# ServoDriverV2.net
KiCad netlist of a schematic drawn in EasyEDA
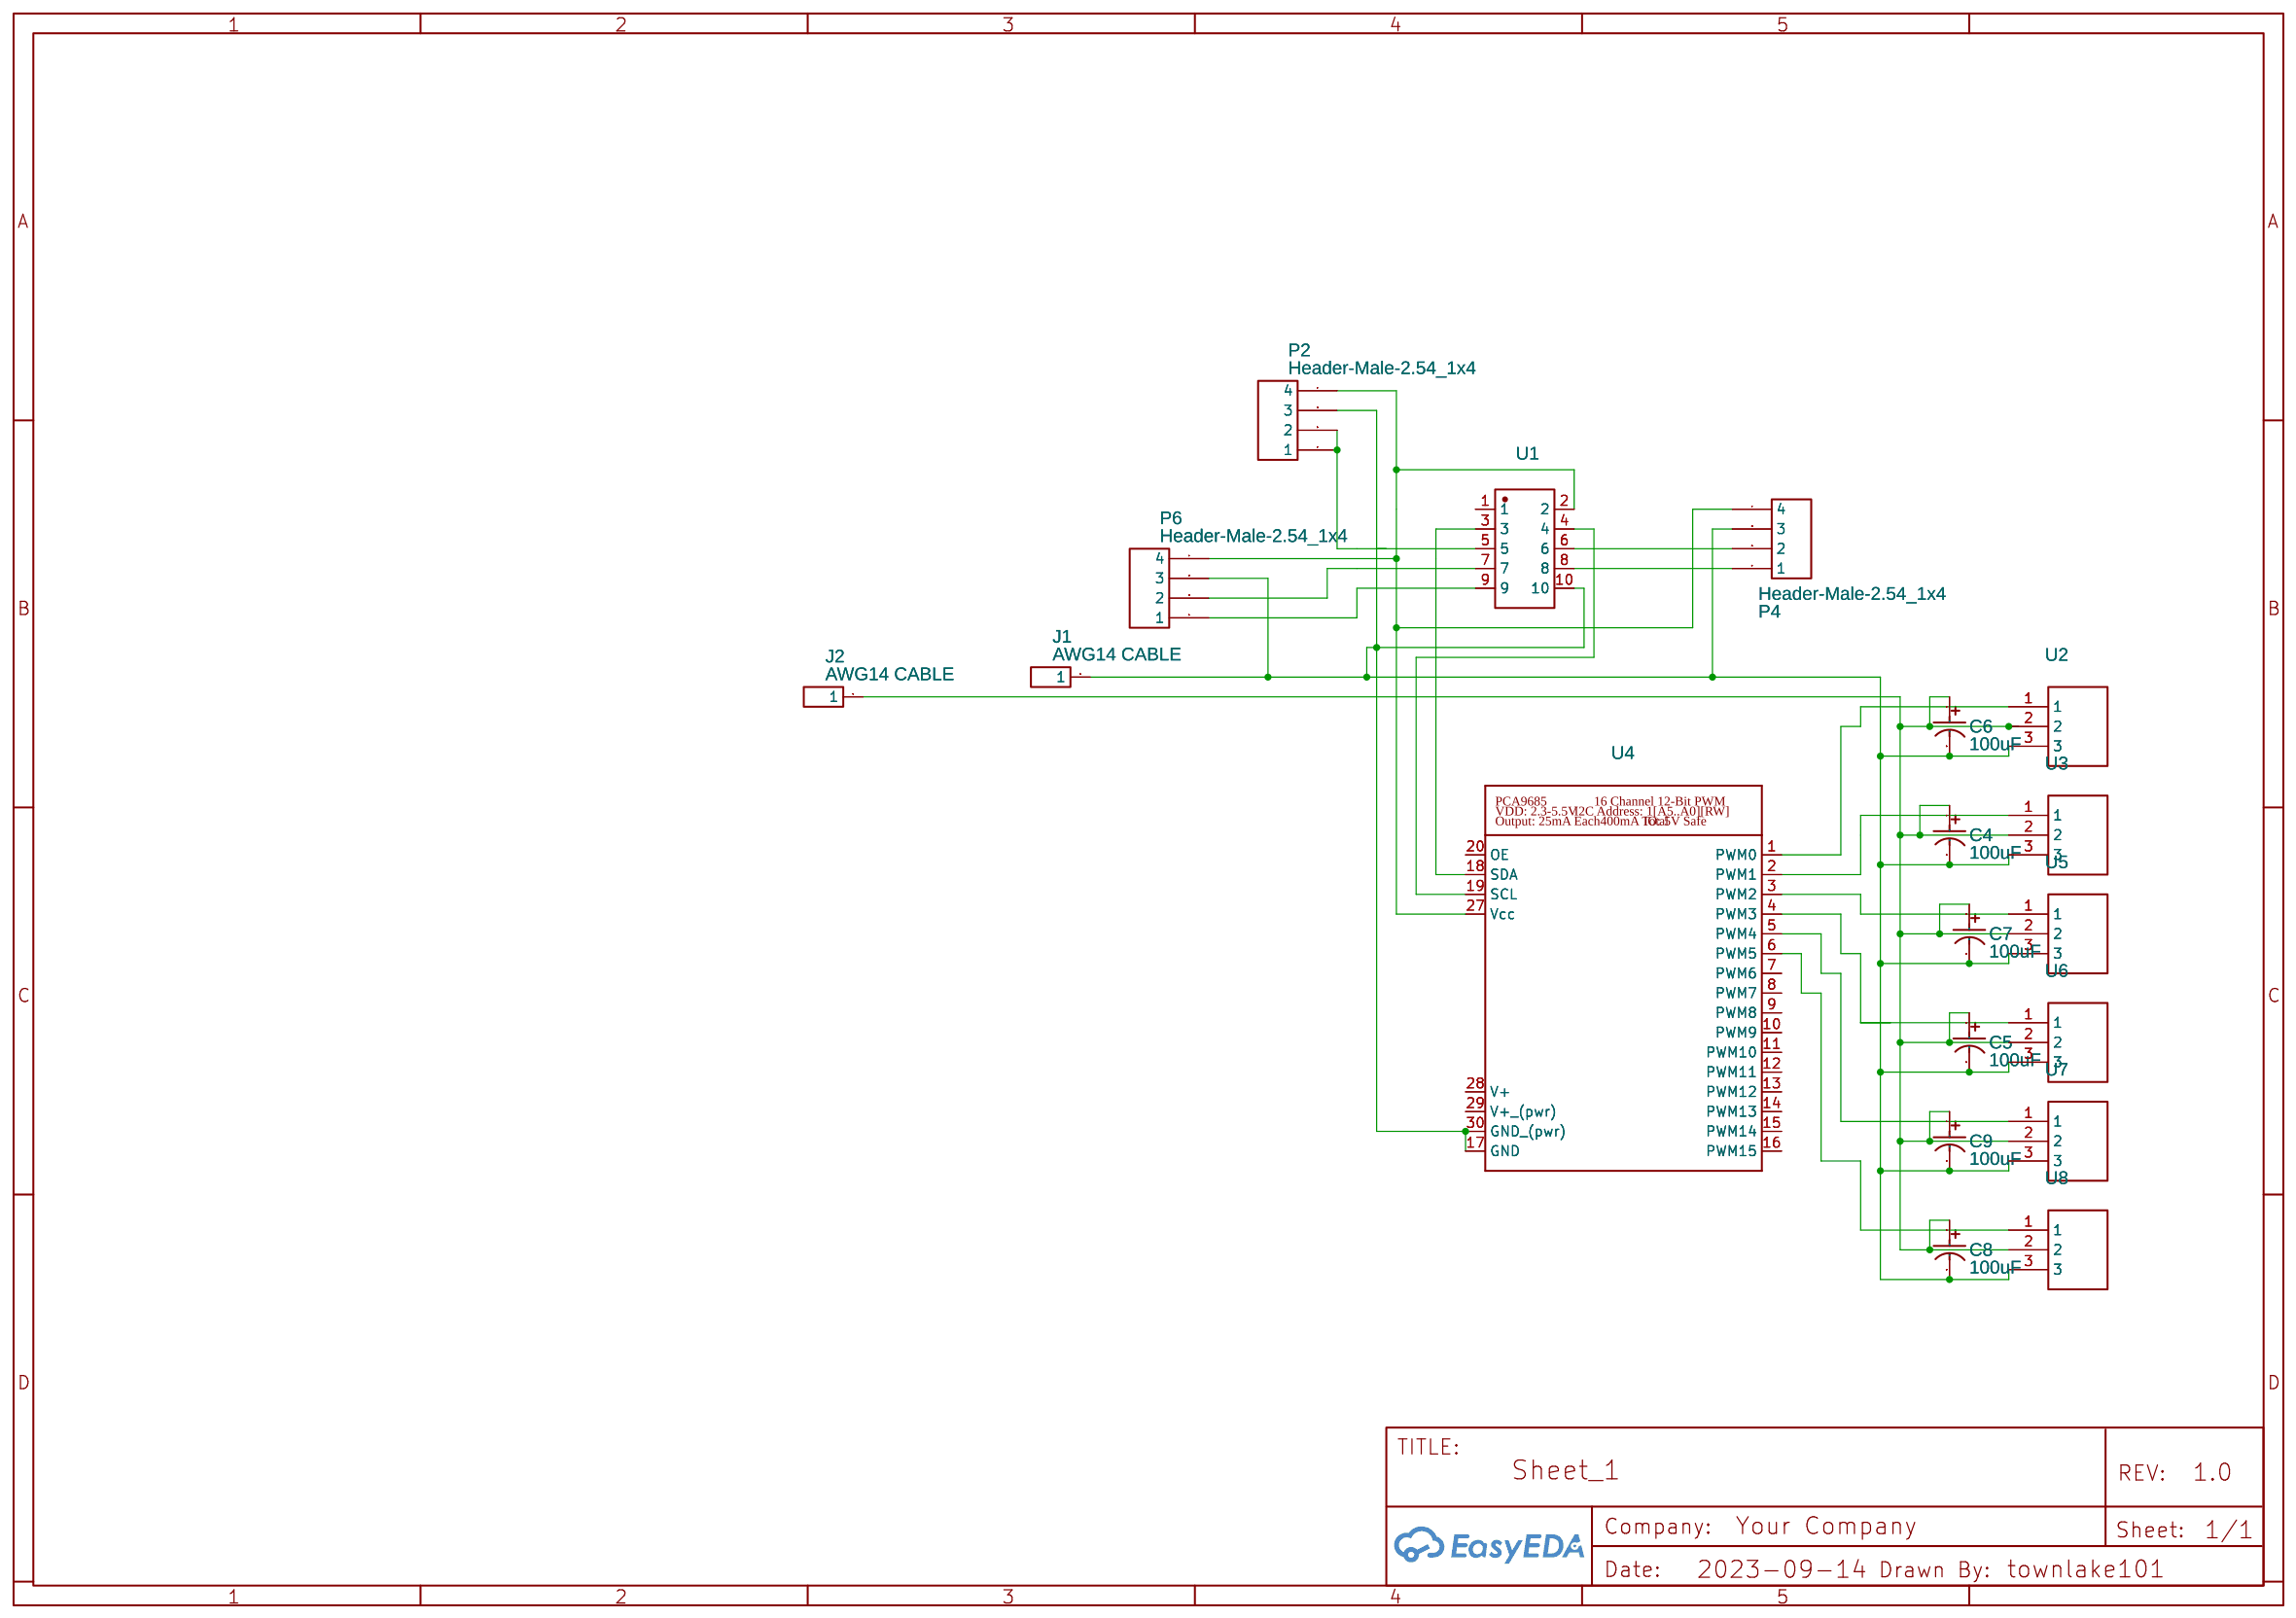
[diagram p0: schematic sheet]

(export (version "E")
  (design (tool "Eeschema 10.0.6"))
  (components
    (comp (ref "C4")
      (value "100uF")
      (fields (field (name "Manufacturer Part") "Jweo"))
      (libsource (lib "") (part "CAP-POL-1"))
    )
    (comp (ref "C5")
      (value "100uF")
      (fields (field (name "Manufacturer Part") "Jweo"))
      (libsource (lib "") (part "CAP-POL-1"))
    )
    (comp (ref "C6")
      (value "100uF")
      (fields (field (name "Manufacturer Part") "Jweo"))
      (libsource (lib "") (part "CAP-POL-1"))
    )
    (comp (ref "C7")
      (value "100uF")
      (fields (field (name "Manufacturer Part") "Jweo"))
      (libsource (lib "") (part "CAP-POL-1"))
    )
    (comp (ref "C8")
      (value "100uF")
      (fields (field (name "Manufacturer Part") "Jweo"))
      (libsource (lib "") (part "CAP-POL-1"))
    )
    (comp (ref "C9")
      (value "100uF")
      (fields (field (name "Manufacturer Part") "Jweo"))
      (libsource (lib "") (part "CAP-POL-1"))
    )
    (comp (ref "J1")
      (value "AWG14 CABLE")
      (fields (field (name "Manufacturer Part") "AWG14 HOLE") (field (name "Manufacturer") "PCB"))
      (libsource (lib "") (part "AWG14 CABLE"))
    )
    (comp (ref "J2")
      (value "AWG14 CABLE")
      (fields (field (name "Manufacturer Part") "AWG14 HOLE") (field (name "Manufacturer") "PCB"))
      (libsource (lib "") (part "AWG14 CABLE"))
    )
    (comp (ref "P2")
      (value "Header-Male-2.54_1x4")
      (fields
        (field (name "Manufacturer Part") "Headers  Pins 1*4P")
        (field (name "Manufacturer") "ReliaPro")
      )
      (libsource (lib "") (part "Header-Male-2.54_1x4_1"))
    )
    (comp (ref "P4")
      (value "Header-Male-2.54_1x4")
      (fields
        (field (name "Manufacturer Part") "Headers  Pins 1*4P")
        (field (name "Manufacturer") "ReliaPro")
      )
      (libsource (lib "") (part "Header-Male-2.54_1x4"))
    )
    (comp (ref "P6")
      (value "Header-Male-2.54_1x4")
      (fields
        (field (name "Manufacturer Part") "Headers  Pins 1*4P")
        (field (name "Manufacturer") "ReliaPro")
      )
      (libsource (lib "") (part "Header-Male-2.54_1x4_1"))
    )
    (comp (ref "U1")
      (value "NO")
      (fields
        (field (name "Manufacturer Part") "KH-2.54PH180-2X5P-L8.9")
        (field (name "Manufacturer") "kinghelm(金航标)")
      )
      (libsource (lib "") (part "KH-2.54PH180-2X5P"))
    )
    (comp (ref "U2") (value "NO") (libsource (lib "") (part "conector-3-PINOS")))
    (comp (ref "U3") (value "NO") (libsource (lib "") (part "conector-3-PINOS")))
    (comp (ref "U4") (value "NO") (libsource (lib "") (part "PCA9685_module_mod")))
    (comp (ref "U5") (value "NO") (libsource (lib "") (part "conector-3-PINOS")))
    (comp (ref "U6") (value "NO") (libsource (lib "") (part "conector-3-PINOS")))
    (comp (ref "U7") (value "NO") (libsource (lib "") (part "conector-3-PINOS")))
    (comp (ref "U8") (value "NO") (libsource (lib "") (part "conector-3-PINOS")))
  )
  (nets
    (net (code "1") (name "Net-(C4-Pad1)") (class "Default")
      (node (ref "C4") (pin "1") (pinfunction "1_1") (pintype "input"))
      (node (ref "C5") (pin "1") (pinfunction "1_1") (pintype "input"))
      (node (ref "C6") (pin "1") (pinfunction "1_1") (pintype "input"))
      (node (ref "C7") (pin "1") (pinfunction "1_1") (pintype "input"))
      (node (ref "C8") (pin "1") (pinfunction "1_1") (pintype "input"))
      (node (ref "C9") (pin "1") (pinfunction "1_1") (pintype "input"))
      (node (ref "J2") (pin "1") (pinfunction "1_1") (pintype "input"))
      (node (ref "U2") (pin "2") (pinfunction "2_2") (pintype "unspecified"))
      (node (ref "U3") (pin "2") (pinfunction "2_2") (pintype "unspecified"))
      (node (ref "U5") (pin "2") (pinfunction "2_2") (pintype "unspecified"))
      (node (ref "U6") (pin "2") (pinfunction "2_2") (pintype "unspecified"))
      (node (ref "U7") (pin "2") (pinfunction "2_2") (pintype "unspecified"))
      (node (ref "U8") (pin "2") (pinfunction "2_2") (pintype "unspecified"))
    )
    (net (code "2") (name "Net-(P2-Pad1)") (class "Default")
      (node (ref "P2") (pin "1") (pinfunction "1_1") (pintype "input"))
      (node (ref "P2") (pin "2") (pinfunction "2_2") (pintype "input"))
      (node (ref "U1") (pin "5") (pinfunction "5_5") (pintype "unspecified"))
    )
    (net (code "3") (name "Net-(P4-Pad1)") (class "Default")
      (node (ref "P4") (pin "1") (pinfunction "1_1") (pintype "input"))
      (node (ref "U1") (pin "8") (pinfunction "8_8") (pintype "unspecified"))
    )
    (net (code "4") (name "Net-(P4-Pad2)") (class "Default")
      (node (ref "P4") (pin "2") (pinfunction "2_2") (pintype "input"))
      (node (ref "U1") (pin "6") (pinfunction "6_6") (pintype "unspecified"))
    )
    (net (code "5") (name "Net-(P6-Pad1)") (class "Default")
      (node (ref "P6") (pin "1") (pinfunction "1_1") (pintype "input"))
      (node (ref "U1") (pin "9") (pinfunction "9_9") (pintype "unspecified"))
    )
    (net (code "6") (name "Net-(P6-Pad2)") (class "Default")
      (node (ref "P6") (pin "2") (pinfunction "2_2") (pintype "input"))
      (node (ref "U1") (pin "7") (pinfunction "7_7") (pintype "unspecified"))
    )
    (net (code "7") (name "Net-(U4-GND)") (class "Default")
      (node (ref "C4") (pin "2") (pinfunction "2_2") (pintype "input"))
      (node (ref "C5") (pin "2") (pinfunction "2_2") (pintype "input"))
      (node (ref "C6") (pin "2") (pinfunction "2_2") (pintype "input"))
      (node (ref "C7") (pin "2") (pinfunction "2_2") (pintype "input"))
      (node (ref "C8") (pin "2") (pinfunction "2_2") (pintype "input"))
      (node (ref "C9") (pin "2") (pinfunction "2_2") (pintype "input"))
      (node (ref "J1") (pin "1") (pinfunction "1_1") (pintype "input"))
      (node (ref "P2") (pin "3") (pinfunction "3_3") (pintype "input"))
      (node (ref "P4") (pin "3") (pinfunction "3_3") (pintype "input"))
      (node (ref "P6") (pin "3") (pinfunction "3_3") (pintype "input"))
      (node (ref "U1") (pin "10") (pinfunction "10_10") (pintype "unspecified"))
      (node (ref "U2") (pin "3") (pinfunction "3_3") (pintype "unspecified"))
      (node (ref "U3") (pin "3") (pinfunction "3_3") (pintype "unspecified"))
      (node (ref "U4") (pin "17") (pinfunction "GND_17") (pintype "passive"))
      (node (ref "U4") (pin "30") (pinfunction "GND_(pwr)_30") (pintype "passive"))
      (node (ref "U5") (pin "3") (pinfunction "3_3") (pintype "unspecified"))
      (node (ref "U6") (pin "3") (pinfunction "3_3") (pintype "unspecified"))
      (node (ref "U7") (pin "3") (pinfunction "3_3") (pintype "unspecified"))
      (node (ref "U8") (pin "3") (pinfunction "3_3") (pintype "unspecified"))
    )
    (net (code "8") (name "Net-(U4-PWM0)") (class "Default")
      (node (ref "U2") (pin "1") (pinfunction "1_1") (pintype "unspecified"))
      (node (ref "U4") (pin "1") (pinfunction "PWM0_1") (pintype "output"))
    )
    (net (code "9") (name "Net-(U4-PWM1)") (class "Default")
      (node (ref "U3") (pin "1") (pinfunction "1_1") (pintype "unspecified"))
      (node (ref "U4") (pin "2") (pinfunction "PWM1_2") (pintype "output"))
    )
    (net (code "10") (name "Net-(U4-PWM2)") (class "Default")
      (node (ref "U4") (pin "3") (pinfunction "PWM2_3") (pintype "output"))
      (node (ref "U5") (pin "1") (pinfunction "1_1") (pintype "unspecified"))
    )
    (net (code "11") (name "Net-(U4-PWM3)") (class "Default")
      (node (ref "U4") (pin "4") (pinfunction "PWM3_4") (pintype "output"))
      (node (ref "U6") (pin "1") (pinfunction "1_1") (pintype "unspecified"))
    )
    (net (code "12") (name "Net-(U4-PWM4)") (class "Default")
      (node (ref "U4") (pin "5") (pinfunction "PWM4_5") (pintype "output"))
      (node (ref "U7") (pin "1") (pinfunction "1_1") (pintype "unspecified"))
    )
    (net (code "13") (name "Net-(U4-PWM5)") (class "Default")
      (node (ref "U4") (pin "6") (pinfunction "PWM5_6") (pintype "output"))
      (node (ref "U8") (pin "1") (pinfunction "1_1") (pintype "unspecified"))
    )
    (net (code "14") (name "Net-(U4-SCL)") (class "Default")
      (node (ref "U1") (pin "4") (pinfunction "4_4") (pintype "unspecified"))
      (node (ref "U4") (pin "19") (pinfunction "SCL_19") (pintype "unspecified"))
    )
    (net (code "15") (name "Net-(U4-SDA)") (class "Default")
      (node (ref "U1") (pin "3") (pinfunction "3_3") (pintype "unspecified"))
      (node (ref "U4") (pin "18") (pinfunction "SDA_18") (pintype "unspecified"))
    )
    (net (code "16") (name "Net-(U4-Vcc)") (class "Default")
      (node (ref "P2") (pin "4") (pinfunction "4_4") (pintype "input"))
      (node (ref "P4") (pin "4") (pinfunction "4_4") (pintype "input"))
      (node (ref "P6") (pin "4") (pinfunction "4_4") (pintype "input"))
      (node (ref "U1") (pin "2") (pinfunction "2_2") (pintype "unspecified"))
      (node (ref "U4") (pin "27") (pinfunction "Vcc_27") (pintype "passive"))
    )
    (net (code "17") (name "unconnected-(U1-Pad1)") (class "Default")
      (node (ref "U1") (pin "1") (pinfunction "1_1") (pintype "unspecified"))
    )
    (net (code "18") (name "unconnected-(U4-OE-Pad20)") (class "Default")
      (node (ref "U4") (pin "20") (pinfunction "OE_20") (pintype "input"))
    )
    (net (code "19") (name "unconnected-(U4-PWM6-Pad7)") (class "Default")
      (node (ref "U4") (pin "7") (pinfunction "PWM6_7") (pintype "output"))
    )
    (net (code "20") (name "unconnected-(U4-PWM7-Pad8)") (class "Default")
      (node (ref "U4") (pin "8") (pinfunction "PWM7_8") (pintype "output"))
    )
    (net (code "21") (name "unconnected-(U4-PWM8-Pad9)") (class "Default")
      (node (ref "U4") (pin "9") (pinfunction "PWM8_9") (pintype "output"))
    )
    (net (code "22") (name "unconnected-(U4-PWM9-Pad10)") (class "Default")
      (node (ref "U4") (pin "10") (pinfunction "PWM9_10") (pintype "output"))
    )
    (net (code "23") (name "unconnected-(U4-PWM10-Pad11)") (class "Default")
      (node (ref "U4") (pin "11") (pinfunction "PWM10_11") (pintype "output"))
    )
    (net (code "24") (name "unconnected-(U4-PWM11-Pad12)") (class "Default")
      (node (ref "U4") (pin "12") (pinfunction "PWM11_12") (pintype "output"))
    )
    (net (code "25") (name "unconnected-(U4-PWM12-Pad13)") (class "Default")
      (node (ref "U4") (pin "13") (pinfunction "PWM12_13") (pintype "output"))
    )
    (net (code "26") (name "unconnected-(U4-PWM13-Pad14)") (class "Default")
      (node (ref "U4") (pin "14") (pinfunction "PWM13_14") (pintype "output"))
    )
    (net (code "27") (name "unconnected-(U4-PWM14-Pad15)") (class "Default")
      (node (ref "U4") (pin "15") (pinfunction "PWM14_15") (pintype "output"))
    )
    (net (code "28") (name "unconnected-(U4-PWM15-Pad16)") (class "Default")
      (node (ref "U4") (pin "16") (pinfunction "PWM15_16") (pintype "output"))
    )
    (net (code "29") (name "unconnected-(U4-V+-Pad28)") (class "Default")
      (node (ref "U4") (pin "28") (pinfunction "V+_28") (pintype "passive"))
    )
    (net (code "30") (name "unconnected-(U4-V+_(pwr)-Pad29)") (class "Default")
      (node (ref "U4") (pin "29") (pinfunction "V+_(pwr)_29") (pintype "passive"))
    )
  )
)
